# regulator-SPX3819M5-L.net
KiCad netlist of a schematic drawn in EAGLE
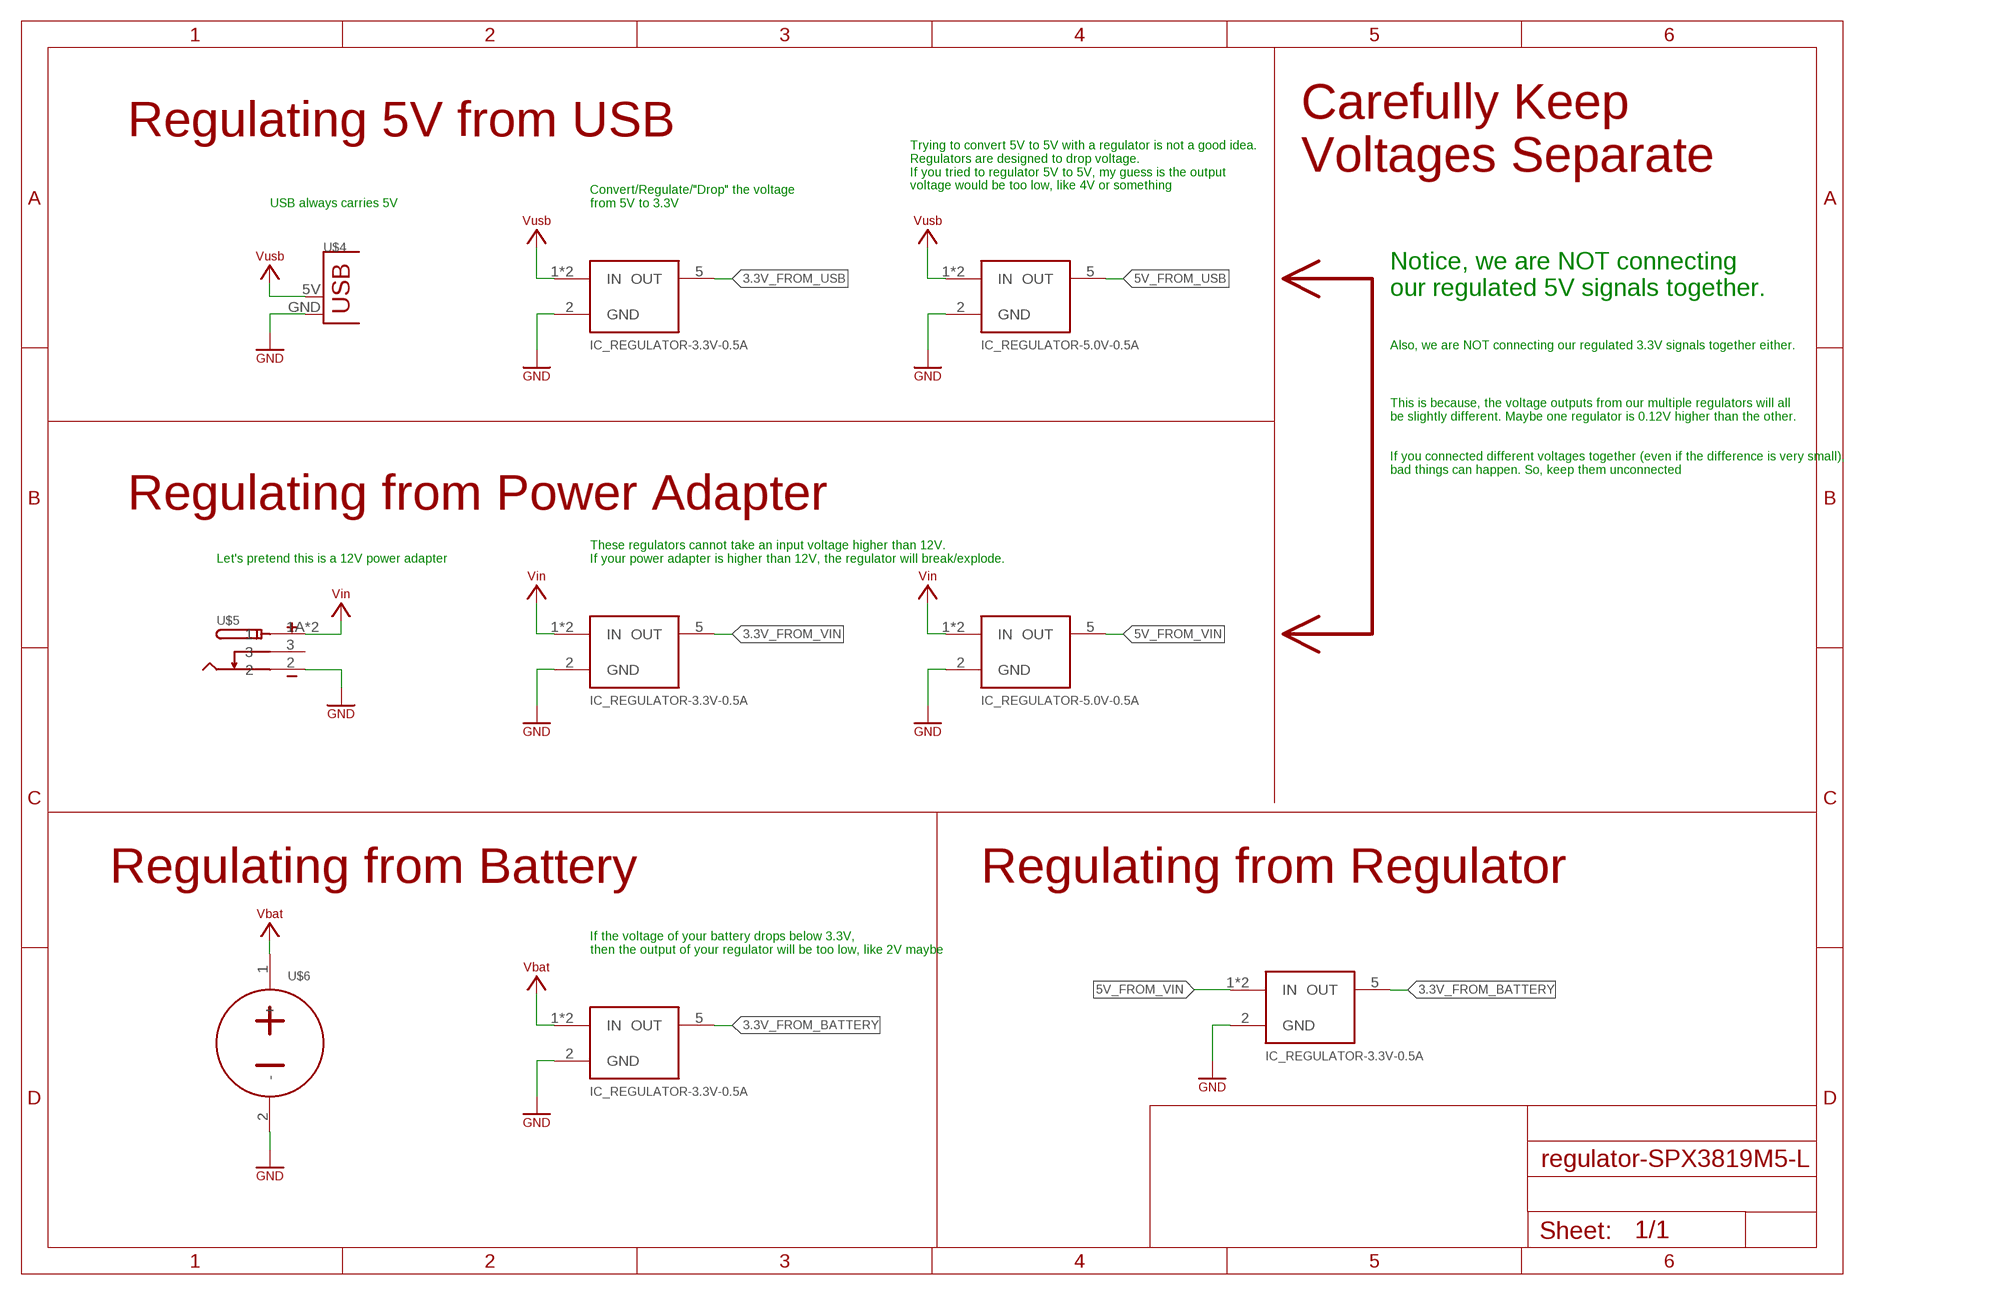
[diagram p0: schematic, sheet 1]

(export (version "E")
  (design (tool "Eeschema 10.0.6"))
  (components
    (comp (ref "U$1")
      (value "IC_REGULATOR-3.3V-0.5A")
      (footprint "eagle-import:SOT23-5")
      (libsource (lib "eagle-import") (part "IC_REGULATOR-3.3V-0.5A"))
    )
    (comp (ref "U$4")
      (value "CONN_USB_PCB_POWER")
      (footprint "eagle-import:USB-PCB-POWER")
      (libsource (lib "eagle-import") (part "CONN_USB_PCB_POWER"))
    )
    (comp (ref "U$5")
      (value "CONN_DC_BARREL-SMD")
      (footprint "eagle-import:694106106102")
      (libsource (lib "eagle-import") (part "CONN_DC_BARREL-SMD"))
    )
    (comp (ref "U$6")
      (value "CONN_BATTERY-LIPO-HORIZ")
      (footprint "eagle-import:JST-PH-2-SMT-RA")
      (libsource (lib "eagle-import") (part "CONN_BATTERY-LIPO-HORIZ"))
    )
    (comp (ref "U$9")
      (value "IC_REGULATOR-3.3V-0.5A")
      (footprint "eagle-import:SOT23-5")
      (libsource (lib "eagle-import") (part "IC_REGULATOR-3.3V-0.5A"))
    )
    (comp (ref "U$11")
      (value "IC_REGULATOR-3.3V-0.5A")
      (footprint "eagle-import:SOT23-5")
      (libsource (lib "eagle-import") (part "IC_REGULATOR-3.3V-0.5A"))
    )
    (comp (ref "U$15")
      (value "IC_REGULATOR-3.3V-0.5A")
      (footprint "eagle-import:SOT23-5")
      (libsource (lib "eagle-import") (part "IC_REGULATOR-3.3V-0.5A"))
    )
    (comp (ref "U$18")
      (value "IC_REGULATOR-5.0V-0.5A")
      (footprint "eagle-import:SOT23-5")
      (libsource (lib "eagle-import") (part "IC_REGULATOR-5.0V-0.5A"))
    )
    (comp (ref "U$19")
      (value "IC_REGULATOR-5.0V-0.5A")
      (footprint "eagle-import:SOT23-5")
      (libsource (lib "eagle-import") (part "IC_REGULATOR-5.0V-0.5A"))
    )
  )
  (nets
    (net (code "1") (name "3.3V_FROM_BATTERY") (class "Default")
      (node (ref "U$15") (pin "5") (pinfunction "OUT_5") (pintype "bidirectional"))
      (node (ref "U$9") (pin "5") (pinfunction "OUT_5") (pintype "bidirectional"))
    )
    (net (code "2") (name "3.3V_FROM_USB") (class "Default")
      (node (ref "U$11") (pin "5") (pinfunction "OUT_5") (pintype "bidirectional"))
    )
    (net (code "3") (name "3.3V_FROM_VIN") (class "Default")
      (node (ref "U$1") (pin "5") (pinfunction "OUT_5") (pintype "bidirectional"))
    )
    (net (code "4") (name "5V_FROM_USB") (class "Default")
      (node (ref "U$19") (pin "5") (pinfunction "OUT_5") (pintype "bidirectional"))
    )
    (net (code "5") (name "5V_FROM_VIN") (class "Default")
      (node (ref "U$15") (pin "1") (pinfunction "IN_1") (pintype "bidirectional"))
      (node (ref "U$15") (pin "3") (pinfunction "IN_3") (pintype "bidirectional"))
      (node (ref "U$18") (pin "5") (pinfunction "OUT_5") (pintype "bidirectional"))
    )
    (net (code "6") (name "SYMBOL_GND") (class "Default")
      (node (ref "U$1") (pin "2") (pinfunction "GND_2") (pintype "bidirectional"))
      (node (ref "U$11") (pin "2") (pinfunction "GND_2") (pintype "bidirectional"))
      (node (ref "U$15") (pin "2") (pinfunction "GND_2") (pintype "bidirectional"))
      (node (ref "U$18") (pin "2") (pinfunction "GND_2") (pintype "bidirectional"))
      (node (ref "U$19") (pin "2") (pinfunction "GND_2") (pintype "bidirectional"))
      (node (ref "U$4") (pin "GND") (pinfunction "GND_GND") (pintype "bidirectional"))
      (node (ref "U$5") (pin "2") (pinfunction "2_2") (pintype "bidirectional"))
      (node (ref "U$6") (pin "2") (pinfunction "-_2") (pintype "bidirectional"))
      (node (ref "U$9") (pin "2") (pinfunction "GND_2") (pintype "bidirectional"))
    )
    (net (code "7") (name "SYMBOL_VBAT") (class "Default")
      (node (ref "U$6") (pin "1") (pinfunction "+_1") (pintype "bidirectional"))
      (node (ref "U$9") (pin "1") (pinfunction "IN_1") (pintype "bidirectional"))
      (node (ref "U$9") (pin "3") (pinfunction "IN_3") (pintype "bidirectional"))
    )
    (net (code "8") (name "SYMBOL_VIN") (class "Default")
      (node (ref "U$1") (pin "1") (pinfunction "IN_1") (pintype "bidirectional"))
      (node (ref "U$1") (pin "3") (pinfunction "IN_3") (pintype "bidirectional"))
      (node (ref "U$18") (pin "1") (pinfunction "IN_1") (pintype "bidirectional"))
      (node (ref "U$18") (pin "3") (pinfunction "IN_3") (pintype "bidirectional"))
      (node (ref "U$5") (pin "1A") (pinfunction "1_1A") (pintype "bidirectional"))
      (node (ref "U$5") (pin "1B") (pinfunction "1_1B") (pintype "bidirectional"))
    )
    (net (code "9") (name "SYMBOL_VUSB") (class "Default")
      (node (ref "U$11") (pin "1") (pinfunction "IN_1") (pintype "bidirectional"))
      (node (ref "U$11") (pin "3") (pinfunction "IN_3") (pintype "bidirectional"))
      (node (ref "U$19") (pin "1") (pinfunction "IN_1") (pintype "bidirectional"))
      (node (ref "U$19") (pin "3") (pinfunction "IN_3") (pintype "bidirectional"))
      (node (ref "U$4") (pin "5V") (pinfunction "VBUS_5V") (pintype "bidirectional"))
    )
    (net (code "10") (name "unconnected-(U$5-Pad3)") (class "Default")
      (node (ref "U$5") (pin "3") (pinfunction "3_3") (pintype "bidirectional"))
    )
  )
)
